# MedHubV1.net
KiCad netlist of a schematic drawn in EAGLE
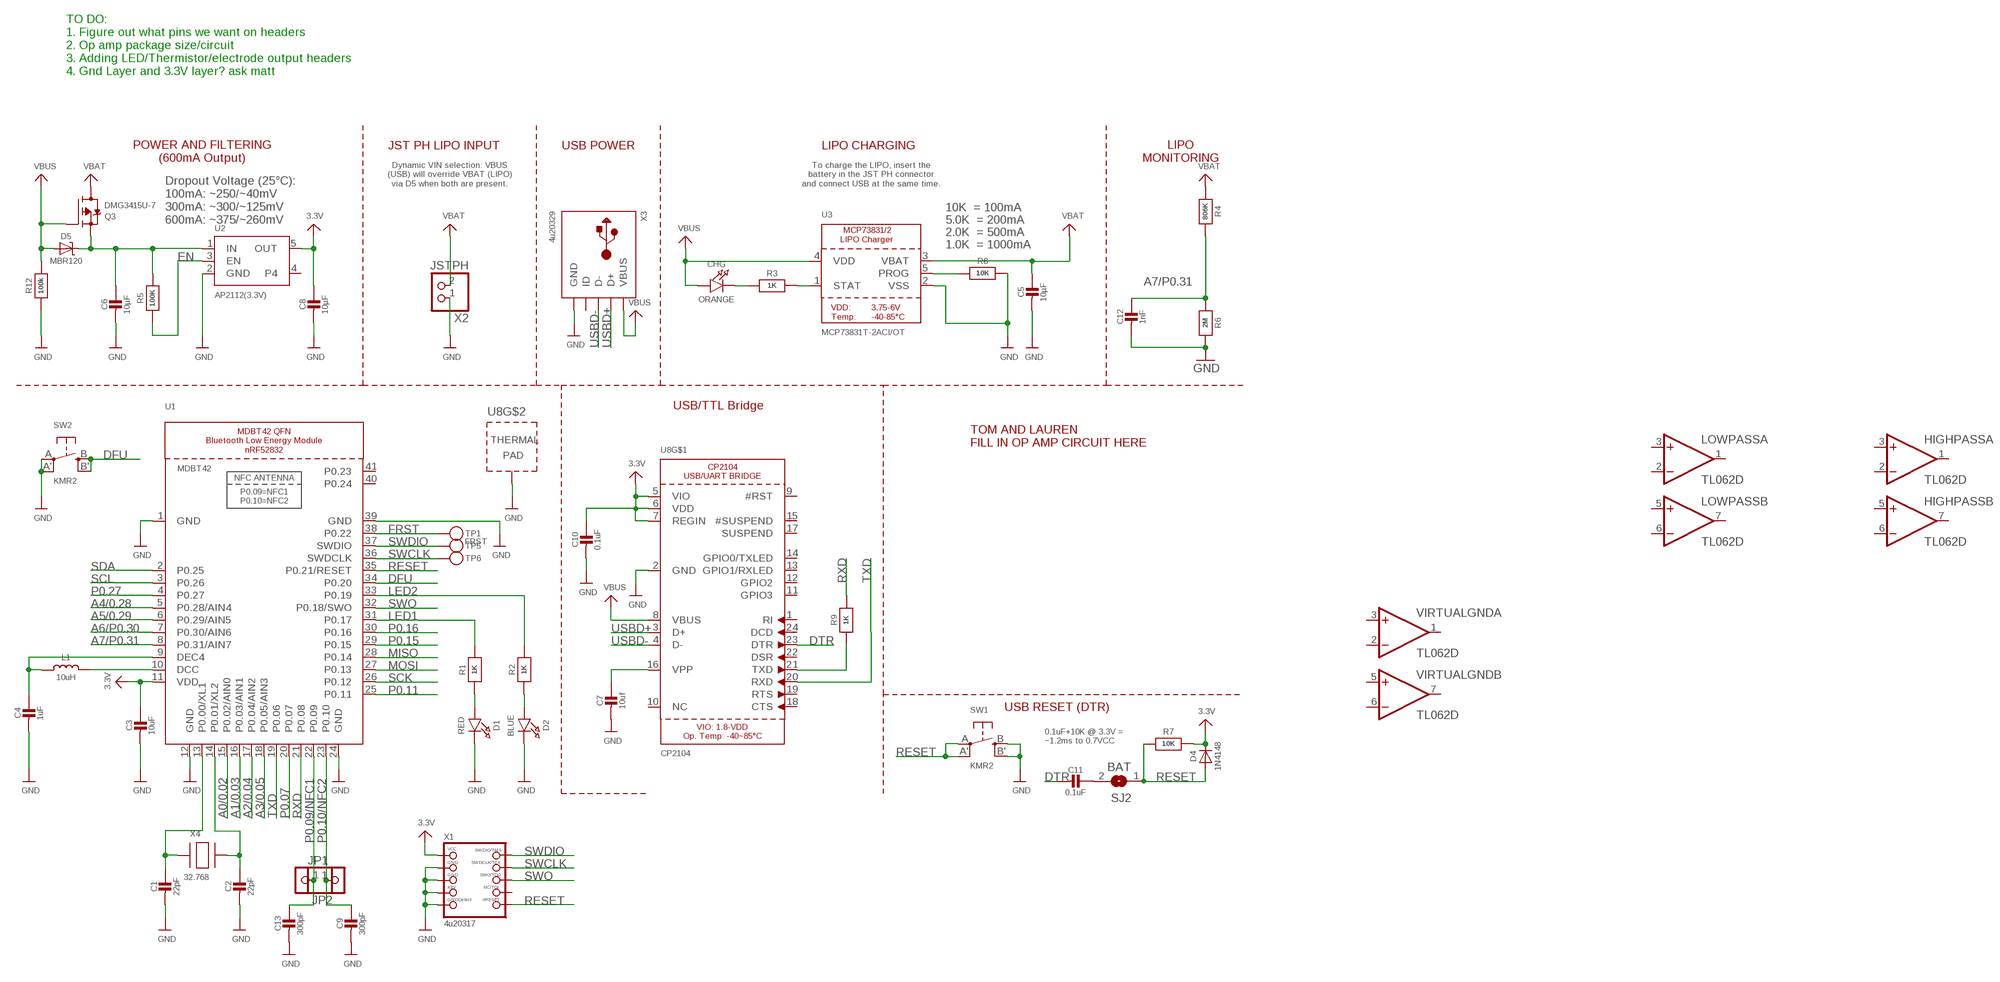
[diagram p0: schematic, sheet 1]

(export (version "E")
  (design (tool "Eeschema 10.0.6"))
  (components
    (comp (ref "C1")
      (value "22pF")
      (footprint "eagle-import:0603-NO")
      (libsource (lib "eagle-import") (part "CAP_CERAMIC0603_NO"))
    )
    (comp (ref "C2")
      (value "22pF")
      (footprint "eagle-import:0603-NO")
      (libsource (lib "eagle-import") (part "CAP_CERAMIC0603_NO"))
    )
    (comp (ref "C3")
      (value "10uF")
      (footprint "eagle-import:0805-NO")
      (libsource (lib "eagle-import") (part "CAP_CERAMIC0805-NOOUTLINE"))
    )
    (comp (ref "C4")
      (value "1uF")
      (footprint "eagle-import:0603-NO")
      (libsource (lib "eagle-import") (part "CAP_CERAMIC0603_NO"))
    )
    (comp (ref "C5")
      (value "10µF")
      (footprint "eagle-import:0805-NO")
      (libsource (lib "eagle-import") (part "CAP_CERAMIC0805-NOOUTLINE"))
    )
    (comp (ref "C6")
      (value "10µF")
      (footprint "eagle-import:0805-NO")
      (libsource (lib "eagle-import") (part "CAP_CERAMIC0805-NOOUTLINE"))
    )
    (comp (ref "C7")
      (value "10uf")
      (footprint "eagle-import:0805-NO")
      (libsource (lib "eagle-import") (part "CAP_CERAMIC0805-NOOUTLINE"))
    )
    (comp (ref "C8")
      (value "10µF")
      (footprint "eagle-import:0805-NO")
      (libsource (lib "eagle-import") (part "CAP_CERAMIC0805-NOOUTLINE"))
    )
    (comp (ref "C9")
      (value "300pF")
      (footprint "eagle-import:_0603MP")
      (libsource (lib "eagle-import") (part "CAP_CERAMIC_0603MP"))
    )
    (comp (ref "C10")
      (value "0.1uF")
      (footprint "eagle-import:0603-NO")
      (libsource (lib "eagle-import") (part "CAP_CERAMIC0603_NO"))
    )
    (comp (ref "C11")
      (value "0.1uF")
      (footprint "eagle-import:0603-NO")
      (libsource (lib "eagle-import") (part "CAP_CERAMIC0603_NO"))
    )
    (comp (ref "C12")
      (value "1nF")
      (footprint "eagle-import:0603-NO")
      (libsource (lib "eagle-import") (part "CAP_CERAMIC0603_NO"))
    )
    (comp (ref "C13")
      (value "300pF")
      (footprint "eagle-import:_0603MP")
      (libsource (lib "eagle-import") (part "CAP_CERAMIC_0603MP"))
    )
    (comp (ref "CHG")
      (value "ORANGE")
      (footprint "eagle-import:CHIPLED_0805_NOOUTLINE")
      (libsource (lib "eagle-import") (part "LED0805_NOOUTLINE"))
    )
    (comp (ref "D1")
      (value "RED")
      (footprint "eagle-import:CHIPLED_0805_NOOUTLINE")
      (libsource (lib "eagle-import") (part "LED0805_NOOUTLINE"))
    )
    (comp (ref "D2")
      (value "BLUE")
      (footprint "eagle-import:CHIPLED_0805_NOOUTLINE")
      (libsource (lib "eagle-import") (part "LED0805_NOOUTLINE"))
    )
    (comp (ref "D4")
      (value "1N4148")
      (footprint "eagle-import:SOD-323")
      (libsource (lib "eagle-import") (part "DIODESOD-323"))
    )
    (comp (ref "D5")
      (value "MBR120")
      (footprint "eagle-import:SOD-123")
      (libsource (lib "eagle-import") (part "DIODE-SCHOTTKYSOD-123"))
    )
    (comp (ref "HIGHPASS")
      (value "TL062D")
      (footprint "eagle-import:SO08")
      (libsource (lib "eagle-import") (part "TL062D"))
    )
    (comp (ref "JP1")
      (value "HEADER-1X12MM")
      (footprint "eagle-import:1X01_2MM")
      (libsource (lib "eagle-import") (part "HEADER-1X12MM"))
    )
    (comp (ref "JP2")
      (value "HEADER-1X12MM")
      (footprint "eagle-import:1X01_2MM")
      (libsource (lib "eagle-import") (part "HEADER-1X12MM"))
    )
    (comp (ref "L1")
      (value "10uH")
      (footprint "eagle-import:0805-NO")
      (libsource (lib "eagle-import") (part "INDUCTOR0805-NO"))
    )
    (comp (ref "LOWPASS")
      (value "TL062D")
      (footprint "eagle-import:SO08")
      (libsource (lib "eagle-import") (part "TL062D"))
    )
    (comp (ref "Q3")
      (value "DMG3415U-7")
      (footprint "eagle-import:SOT23-R")
      (libsource (lib "eagle-import") (part "MOSFET-P"))
    )
    (comp (ref "R1")
      (value "1K")
      (footprint "eagle-import:0603-NO")
      (libsource (lib "eagle-import") (part "RESISTOR_0603_NOOUT"))
    )
    (comp (ref "R2")
      (value "1K")
      (footprint "eagle-import:0603-NO")
      (libsource (lib "eagle-import") (part "RESISTOR_0603_NOOUT"))
    )
    (comp (ref "R3")
      (value "1K")
      (footprint "eagle-import:0603-NO")
      (libsource (lib "eagle-import") (part "RESISTOR_0603_NOOUT"))
    )
    (comp (ref "R4")
      (value "806K")
      (footprint "eagle-import:0603-NO")
      (libsource (lib "eagle-import") (part "RESISTOR_0603_NOOUT"))
    )
    (comp (ref "R5")
      (value "100K")
      (footprint "eagle-import:0603-NO")
      (libsource (lib "eagle-import") (part "RESISTOR_0603_NOOUT"))
    )
    (comp (ref "R6")
      (value "2M")
      (footprint "eagle-import:0603-NO")
      (libsource (lib "eagle-import") (part "RESISTOR_0603_NOOUT"))
    )
    (comp (ref "R7")
      (value "10K")
      (footprint "eagle-import:0603-NO")
      (libsource (lib "eagle-import") (part "RESISTOR_0603_NOOUT"))
    )
    (comp (ref "R8")
      (value "10K")
      (footprint "eagle-import:0603-NO")
      (libsource (lib "eagle-import") (part "RESISTOR_0603_NOOUT"))
    )
    (comp (ref "R9")
      (value "1K")
      (footprint "eagle-import:0603-NO")
      (libsource (lib "eagle-import") (part "RESISTOR_0603_NOOUT"))
    )
    (comp (ref "R12")
      (value "100k")
      (footprint "eagle-import:0603-NO")
      (libsource (lib "eagle-import") (part "RESISTOR_0603_NOOUT"))
    )
    (comp (ref "SJ2")
      (value "BAT")
      (footprint "eagle-import:SOLDERJUMPER_CLOSEDWIRE")
      (libsource (lib "eagle-import") (part "SOLDERJUMPERCLOSED"))
    )
    (comp (ref "SW1")
      (value "KMR2")
      (footprint "eagle-import:BTN_KMR2_4.6X2.8")
      (libsource (lib "eagle-import") (part "SWITCH_TACT_SMT4.6X2.8"))
    )
    (comp (ref "SW2")
      (value "KMR2")
      (footprint "eagle-import:BTN_KMR2_4.6X2.8")
      (libsource (lib "eagle-import") (part "SWITCH_TACT_SMT4.6X2.8"))
    )
    (comp (ref "TP1")
      (value "FRST")
      (footprint "eagle-import:PAD-1.5X2.0")
      (libsource (lib "eagle-import") (part "TESTPOINT1.5X2.0MM_NOCREAM"))
    )
    (comp (ref "TP5")
      (value "TESTPOINTROUND2MM")
      (footprint "eagle-import:TESTPOINT_ROUND_2MM")
      (libsource (lib "eagle-import") (part "TESTPOINTROUND2MM"))
    )
    (comp (ref "TP6")
      (value "TESTPOINTROUND2MM")
      (footprint "eagle-import:TESTPOINT_ROUND_2MM")
      (libsource (lib "eagle-import") (part "TESTPOINTROUND2MM"))
    )
    (comp (ref "U1")
      (value "MDBT42")
      (footprint "eagle-import:BLE_MODULE_RAYTAC_MDBT42")
      (libsource (lib "eagle-import") (part "NRF52832_MODULE_MDBT42"))
    )
    (comp (ref "U2")
      (value "AP2112(3.3V)")
      (footprint "eagle-import:SOT23-5")
      (libsource (lib "eagle-import") (part "VREG_SOT23-5"))
    )
    (comp (ref "U3")
      (value "MCP73831T-2ACI/OT")
      (footprint "eagle-import:SOT23-5")
      (libsource (lib "eagle-import") (part "MCP73831/2"))
    )
    (comp (ref "U8")
      (value "CP2104")
      (footprint "eagle-import:QFN24_4MM_SMSC")
      (libsource (lib "eagle-import") (part "CP2104"))
    )
    (comp (ref "VIRTUALGND")
      (value "TL062D")
      (footprint "eagle-import:SO08")
      (libsource (lib "eagle-import") (part "TL062D"))
    )
    (comp (ref "X1")
      (value "4u20317")
      (footprint "eagle-import:2X05_1.27MM_BOX_POSTS")
      (libsource (lib "eagle-import") (part "JTAG-CORTEXBOXPOSTS"))
    )
    (comp (ref "X2")
      (value "JSTPH")
      (footprint "eagle-import:JSTPH2")
      (libsource (lib "eagle-import") (part "CON_JST_PH_2PIN"))
    )
    (comp (ref "X3")
      (value "4u20329")
      (footprint "eagle-import:4UCONN_20329_V2")
      (libsource (lib "eagle-import") (part "USB_MICRO_20329_V2"))
    )
    (comp (ref "X4")
      (value "32.768")
      (footprint "eagle-import:XTAL3215")
      (libsource (lib "eagle-import") (part "XTAL-3.2X1.5"))
    )
  )
  (nets
    (net (code "1") (name "/A0{slash}0.02") (class "Default")
      (node (ref "U1") (pin "15") (pinfunction "P0.02/AIN0_15") (pintype "bidirectional"))
    )
    (net (code "2") (name "/A1{slash}0.03") (class "Default")
      (node (ref "U1") (pin "16") (pinfunction "P0.03/AIN1_16") (pintype "bidirectional"))
    )
    (net (code "3") (name "/A2{slash}0.04") (class "Default")
      (node (ref "U1") (pin "17") (pinfunction "P0.04/AIN2_17") (pintype "bidirectional"))
    )
    (net (code "4") (name "/A3{slash}0.05") (class "Default")
      (node (ref "U1") (pin "18") (pinfunction "P0.05/AIN3_18") (pintype "bidirectional"))
    )
    (net (code "5") (name "/A4{slash}0.28") (class "Default")
      (node (ref "U1") (pin "5") (pinfunction "P0.28/AIN4_5") (pintype "bidirectional"))
    )
    (net (code "6") (name "/A5{slash}0.29") (class "Default")
      (node (ref "U1") (pin "6") (pinfunction "P0.29/AIN5_6") (pintype "bidirectional"))
    )
    (net (code "7") (name "/A6{slash}P0.30") (class "Default")
      (node (ref "U1") (pin "7") (pinfunction "P0.30/AIN6_7") (pintype "bidirectional"))
    )
    (net (code "8") (name "/A7{slash}P0.31") (class "Default")
      (node (ref "C12") (pin "1") (pinfunction "1_1") (pintype "passive"))
      (node (ref "R4") (pin "2") (pinfunction "2_2") (pintype "passive"))
      (node (ref "R6") (pin "1") (pinfunction "1_1") (pintype "passive"))
      (node (ref "U1") (pin "8") (pinfunction "P0.31/AIN7_8") (pintype "bidirectional"))
    )
    (net (code "9") (name "/DFU") (class "Default")
      (node (ref "SW2") (pin "B") (pinfunction "S_B") (pintype "passive"))
      (node (ref "SW2") (pin "B'") (pinfunction "S1_B'") (pintype "passive"))
      (node (ref "U1") (pin "34") (pinfunction "P0.20_34") (pintype "bidirectional"))
    )
    (net (code "10") (name "/DTR") (class "Default")
      (node (ref "C11") (pin "2") (pinfunction "2_2") (pintype "passive"))
      (node (ref "U8") (pin "23") (pinfunction "DTR_23") (pintype "output"))
    )
    (net (code "11") (name "/EN") (class "Default")
      (node (ref "R5") (pin "1") (pinfunction "1_1") (pintype "passive"))
      (node (ref "U2") (pin "3") (pinfunction "EN_3") (pintype "input"))
    )
    (net (code "12") (name "/FRST") (class "Default")
      (node (ref "TP1") (pin "P$1") (pinfunction "P$1_P$1") (pintype "bidirectional"))
      (node (ref "U1") (pin "38") (pinfunction "P0.22_38") (pintype "bidirectional"))
    )
    (net (code "13") (name "/LED1") (class "Default")
      (node (ref "R1") (pin "2") (pinfunction "2_2") (pintype "passive"))
      (node (ref "U1") (pin "31") (pinfunction "P0.17_31") (pintype "bidirectional"))
    )
    (net (code "14") (name "/LED2") (class "Default")
      (node (ref "R2") (pin "2") (pinfunction "2_2") (pintype "passive"))
      (node (ref "U1") (pin "33") (pinfunction "P0.19_33") (pintype "bidirectional"))
    )
    (net (code "15") (name "/MISO") (class "Default")
      (node (ref "U1") (pin "28") (pinfunction "P0.14_28") (pintype "bidirectional"))
    )
    (net (code "16") (name "/MOSI") (class "Default")
      (node (ref "U1") (pin "27") (pinfunction "P0.13_27") (pintype "bidirectional"))
    )
    (net (code "17") (name "/P0.07") (class "Default")
      (node (ref "U1") (pin "20") (pinfunction "P0.07_20") (pintype "bidirectional"))
    )
    (net (code "18") (name "/P0.09{slash}NFC1") (class "Default")
      (node (ref "C13") (pin "1") (pinfunction "1_1") (pintype "passive"))
      (node (ref "JP2") (pin "1") (pinfunction "1_1") (pintype "passive"))
      (node (ref "U1") (pin "22") (pinfunction "P0.09_22") (pintype "bidirectional"))
    )
    (net (code "19") (name "/P0.10{slash}NFC2") (class "Default")
      (node (ref "C9") (pin "1") (pinfunction "1_1") (pintype "passive"))
      (node (ref "JP1") (pin "1") (pinfunction "1_1") (pintype "passive"))
      (node (ref "U1") (pin "23") (pinfunction "P0.10_23") (pintype "bidirectional"))
    )
    (net (code "20") (name "/P0.11") (class "Default")
      (node (ref "U1") (pin "25") (pinfunction "P0.11_25") (pintype "bidirectional"))
    )
    (net (code "21") (name "/P0.15") (class "Default")
      (node (ref "U1") (pin "29") (pinfunction "P0.15_29") (pintype "bidirectional"))
    )
    (net (code "22") (name "/P0.16") (class "Default")
      (node (ref "U1") (pin "30") (pinfunction "P0.16_30") (pintype "bidirectional"))
    )
    (net (code "23") (name "/P0.27") (class "Default")
      (node (ref "U1") (pin "4") (pinfunction "P0.27_4") (pintype "bidirectional"))
    )
    (net (code "24") (name "/RESET") (class "Default")
      (node (ref "D4") (pin "A") (pinfunction "A_A") (pintype "passive"))
      (node (ref "R7") (pin "1") (pinfunction "1_1") (pintype "passive"))
      (node (ref "SJ2") (pin "1") (pinfunction "1_1") (pintype "passive"))
      (node (ref "SW1") (pin "A") (pinfunction "P_A") (pintype "passive"))
      (node (ref "SW1") (pin "A'") (pinfunction "P1_A'") (pintype "passive"))
      (node (ref "U1") (pin "35") (pinfunction "P0.21/RESET_35") (pintype "bidirectional"))
      (node (ref "X1") (pin "10") (pinfunction "NRESET_10") (pintype "bidirectional"))
    )
    (net (code "25") (name "/RXD") (class "Default")
      (node (ref "R9") (pin "2") (pinfunction "2_2") (pintype "passive"))
      (node (ref "U1") (pin "21") (pinfunction "P0.08_21") (pintype "bidirectional"))
    )
    (net (code "26") (name "/SCK") (class "Default")
      (node (ref "U1") (pin "26") (pinfunction "P0.12_26") (pintype "bidirectional"))
    )
    (net (code "27") (name "/SCL") (class "Default")
      (node (ref "U1") (pin "3") (pinfunction "P0.26_3") (pintype "bidirectional"))
    )
    (net (code "28") (name "/SDA") (class "Default")
      (node (ref "U1") (pin "2") (pinfunction "P0.25_2") (pintype "bidirectional"))
    )
    (net (code "29") (name "/SWCLK") (class "Default")
      (node (ref "TP6") (pin "P$1") (pinfunction "P$1_P$1") (pintype "bidirectional"))
      (node (ref "U1") (pin "36") (pinfunction "SWDCLK_36") (pintype "bidirectional"))
      (node (ref "X1") (pin "4") (pinfunction "SWDCLK_4") (pintype "bidirectional"))
    )
    (net (code "30") (name "/SWDIO") (class "Default")
      (node (ref "TP5") (pin "P$1") (pinfunction "P$1_P$1") (pintype "bidirectional"))
      (node (ref "U1") (pin "37") (pinfunction "SWDIO_37") (pintype "bidirectional"))
      (node (ref "X1") (pin "2") (pinfunction "SWDIO_2") (pintype "bidirectional"))
    )
    (net (code "31") (name "/SWO") (class "Default")
      (node (ref "U1") (pin "32") (pinfunction "P0.18/SWO_32") (pintype "bidirectional"))
      (node (ref "X1") (pin "6") (pinfunction "SWO_6") (pintype "bidirectional"))
    )
    (net (code "32") (name "/TXD") (class "Default")
      (node (ref "U1") (pin "19") (pinfunction "P0.06_19") (pintype "bidirectional"))
      (node (ref "U8") (pin "20") (pinfunction "RXD_20") (pintype "input"))
    )
    (net (code "33") (name "/USBD+") (class "Default")
      (node (ref "U8") (pin "3") (pinfunction "D+_3") (pintype "bidirectional"))
      (node (ref "X3") (pin "D+") (pinfunction "D+_D+") (pintype "bidirectional"))
    )
    (net (code "34") (name "/USBD-") (class "Default")
      (node (ref "U8") (pin "4") (pinfunction "D-_4") (pintype "bidirectional"))
      (node (ref "X3") (pin "D-") (pinfunction "D-_D-") (pintype "bidirectional"))
    )
    (net (code "35") (name "3.3V") (class "Default")
      (node (ref "C10") (pin "1") (pinfunction "1_1") (pintype "passive"))
      (node (ref "C3") (pin "1") (pinfunction "1_1") (pintype "passive"))
      (node (ref "C8") (pin "1") (pinfunction "1_1") (pintype "passive"))
      (node (ref "D4") (pin "C") (pinfunction "C_C") (pintype "passive"))
      (node (ref "R7") (pin "2") (pinfunction "2_2") (pintype "passive"))
      (node (ref "U1") (pin "11") (pinfunction "VDD_11") (pintype "bidirectional"))
      (node (ref "U2") (pin "5") (pinfunction "OUT_5") (pintype "power_in"))
      (node (ref "U8") (pin "5") (pinfunction "VIO_5") (pintype "power_in"))
      (node (ref "U8") (pin "6") (pinfunction "VDD_6") (pintype "power_in"))
      (node (ref "U8") (pin "7") (pinfunction "REGIN_7") (pintype "power_in"))
      (node (ref "X1") (pin "1") (pinfunction "VCC_1") (pintype "power_in"))
    )
    (net (code "36") (name "GND") (class "Default")
      (node (ref "C1") (pin "2") (pinfunction "2_2") (pintype "passive"))
      (node (ref "C10") (pin "2") (pinfunction "2_2") (pintype "passive"))
      (node (ref "C12") (pin "2") (pinfunction "2_2") (pintype "passive"))
      (node (ref "C13") (pin "2") (pinfunction "2_2") (pintype "passive"))
      (node (ref "C2") (pin "2") (pinfunction "2_2") (pintype "passive"))
      (node (ref "C3") (pin "2") (pinfunction "2_2") (pintype "passive"))
      (node (ref "C4") (pin "2") (pinfunction "2_2") (pintype "passive"))
      (node (ref "C5") (pin "2") (pinfunction "2_2") (pintype "passive"))
      (node (ref "C6") (pin "2") (pinfunction "2_2") (pintype "passive"))
      (node (ref "C7") (pin "2") (pinfunction "2_2") (pintype "passive"))
      (node (ref "C8") (pin "2") (pinfunction "2_2") (pintype "passive"))
      (node (ref "C9") (pin "2") (pinfunction "2_2") (pintype "passive"))
      (node (ref "D1") (pin "C") (pinfunction "C_C") (pintype "passive"))
      (node (ref "D2") (pin "C") (pinfunction "C_C") (pintype "passive"))
      (node (ref "R12") (pin "1") (pinfunction "1_1") (pintype "passive"))
      (node (ref "R6") (pin "2") (pinfunction "2_2") (pintype "passive"))
      (node (ref "R8") (pin "2") (pinfunction "2_2") (pintype "passive"))
      (node (ref "SW1") (pin "B") (pinfunction "S_B") (pintype "passive"))
      (node (ref "SW1") (pin "B'") (pinfunction "S1_B'") (pintype "passive"))
      (node (ref "SW2") (pin "A") (pinfunction "P_A") (pintype "passive"))
      (node (ref "SW2") (pin "A'") (pinfunction "P1_A'") (pintype "passive"))
      (node (ref "U1") (pin "1") (pinfunction "GND_1") (pintype "bidirectional"))
      (node (ref "U1") (pin "12") (pinfunction "GND_12") (pintype "bidirectional"))
      (node (ref "U1") (pin "24") (pinfunction "GND_24") (pintype "bidirectional"))
      (node (ref "U1") (pin "39") (pinfunction "GND_39") (pintype "bidirectional"))
      (node (ref "U2") (pin "2") (pinfunction "GND_2") (pintype "power_in"))
      (node (ref "U3") (pin "2") (pinfunction "VSS_2") (pintype "power_in"))
      (node (ref "U8") (pin "2") (pinfunction "GND_2") (pintype "power_in"))
      (node (ref "U8") (pin "THERM") (pinfunction "TP_THERM") (pintype "power_in"))
      (node (ref "X1") (pin "3") (pinfunction "GND_3") (pintype "power_in"))
      (node (ref "X1") (pin "5") (pinfunction "GND_5") (pintype "power_in"))
      (node (ref "X1") (pin "7") (pinfunction "KEY_7") (pintype "bidirectional"))
      (node (ref "X1") (pin "9") (pinfunction "GNDDETECT_9") (pintype "bidirectional"))
      (node (ref "X2") (pin "1") (pinfunction "1_1") (pintype "passive"))
      (node (ref "X3") (pin "BASE@1") (pinfunction "GND_BASE@1") (pintype "power_in"))
      (node (ref "X3") (pin "BASE@2") (pinfunction "GND_BASE@2") (pintype "power_in"))
      (node (ref "X3") (pin "GND") (pinfunction "GND_GND") (pintype "power_in"))
      (node (ref "X3") (pin "SPRT@1") (pinfunction "GND_SPRT@1") (pintype "power_in"))
      (node (ref "X3") (pin "SPRT@2") (pinfunction "GND_SPRT@2") (pintype "power_in"))
      (node (ref "X3") (pin "SPRT@3") (pinfunction "GND_SPRT@3") (pintype "power_in"))
      (node (ref "X3") (pin "SPRT@4") (pinfunction "GND_SPRT@4") (pintype "power_in"))
    )
    (net (code "37") (name "Net-(C11-Pad1)") (class "Default")
      (node (ref "C11") (pin "1") (pinfunction "1_1") (pintype "passive"))
      (node (ref "SJ2") (pin "2") (pinfunction "2_2") (pintype "passive"))
    )
    (net (code "38") (name "Net-(CHG-PadC)") (class "Default")
      (node (ref "CHG") (pin "C") (pinfunction "C_C") (pintype "passive"))
      (node (ref "R3") (pin "1") (pinfunction "1_1") (pintype "passive"))
    )
    (net (code "39") (name "Net-(D1-PadA)") (class "Default")
      (node (ref "D1") (pin "A") (pinfunction "A_A") (pintype "passive"))
      (node (ref "R1") (pin "1") (pinfunction "1_1") (pintype "passive"))
    )
    (net (code "40") (name "Net-(D2-PadA)") (class "Default")
      (node (ref "D2") (pin "A") (pinfunction "A_A") (pintype "passive"))
      (node (ref "R2") (pin "1") (pinfunction "1_1") (pintype "passive"))
    )
    (net (code "41") (name "Net-(Q3-S)") (class "Default")
      (node (ref "C6") (pin "1") (pinfunction "1_1") (pintype "passive"))
      (node (ref "D5") (pin "C") (pinfunction "C_C") (pintype "passive"))
      (node (ref "Q3") (pin "2") (pinfunction "S_2") (pintype "passive"))
      (node (ref "R5") (pin "2") (pinfunction "2_2") (pintype "passive"))
      (node (ref "U2") (pin "1") (pinfunction "IN_1") (pintype "power_in"))
    )
    (net (code "42") (name "Net-(U1-DCC)") (class "Default")
      (node (ref "L1") (pin "2") (pinfunction "2_2") (pintype "passive"))
      (node (ref "U1") (pin "10") (pinfunction "DCC_10") (pintype "bidirectional"))
    )
    (net (code "43") (name "Net-(U1-DEC4)") (class "Default")
      (node (ref "C4") (pin "1") (pinfunction "1_1") (pintype "passive"))
      (node (ref "L1") (pin "1") (pinfunction "1_1") (pintype "passive"))
      (node (ref "U1") (pin "9") (pinfunction "DEC4_9") (pintype "bidirectional"))
    )
    (net (code "44") (name "Net-(U1-P0.00{slash}XL1)") (class "Default")
      (node (ref "C1") (pin "1") (pinfunction "1_1") (pintype "passive"))
      (node (ref "U1") (pin "13") (pinfunction "P0.00/XL1_13") (pintype "bidirectional"))
      (node (ref "X4") (pin "P$1") (pinfunction "P$1_P$1") (pintype "bidirectional"))
    )
    (net (code "45") (name "Net-(U1-P0.01{slash}XL2)") (class "Default")
      (node (ref "C2") (pin "1") (pinfunction "1_1") (pintype "passive"))
      (node (ref "U1") (pin "14") (pinfunction "P0.01/XL2_14") (pintype "bidirectional"))
      (node (ref "X4") (pin "P$2") (pinfunction "P$2_P$2") (pintype "bidirectional"))
    )
    (net (code "46") (name "Net-(U3-PROG)") (class "Default")
      (node (ref "R8") (pin "1") (pinfunction "1_1") (pintype "passive"))
      (node (ref "U3") (pin "5") (pinfunction "PROG_5") (pintype "input"))
    )
    (net (code "47") (name "Net-(U3-STAT)") (class "Default")
      (node (ref "R3") (pin "2") (pinfunction "2_2") (pintype "passive"))
      (node (ref "U3") (pin "1") (pinfunction "STAT_1") (pintype "output"))
    )
    (net (code "48") (name "Net-(U8A-TXD)") (class "Default")
      (node (ref "R9") (pin "1") (pinfunction "1_1") (pintype "passive"))
      (node (ref "U8") (pin "21") (pinfunction "TXD_21") (pintype "output"))
    )
    (net (code "49") (name "Net-(U8A-VPP)") (class "Default")
      (node (ref "C7") (pin "1") (pinfunction "1_1") (pintype "passive"))
      (node (ref "U8") (pin "16") (pinfunction "VPP_16") (pintype "bidirectional"))
    )
    (net (code "50") (name "VBAT") (class "Default")
      (node (ref "C5") (pin "1") (pinfunction "1_1") (pintype "passive"))
      (node (ref "Q3") (pin "3") (pinfunction "D_3") (pintype "passive"))
      (node (ref "R4") (pin "1") (pinfunction "1_1") (pintype "passive"))
      (node (ref "U3") (pin "3") (pinfunction "VBAT_3") (pintype "power_in"))
      (node (ref "X2") (pin "2") (pinfunction "2_2") (pintype "passive"))
    )
    (net (code "51") (name "VBUS") (class "Default")
      (node (ref "CHG") (pin "A") (pinfunction "A_A") (pintype "passive"))
      (node (ref "D5") (pin "A") (pinfunction "A_A") (pintype "passive"))
      (node (ref "Q3") (pin "1") (pinfunction "G_1") (pintype "passive"))
      (node (ref "R12") (pin "2") (pinfunction "2_2") (pintype "passive"))
      (node (ref "U3") (pin "4") (pinfunction "VDD_4") (pintype "power_in"))
      (node (ref "U8") (pin "8") (pinfunction "VBUS_8") (pintype "power_in"))
      (node (ref "X3") (pin "VBUS") (pinfunction "VBUS_VBUS") (pintype "power_in"))
    )
    (net (code "52") (name "unconnected-(HIGHPASSA-+IN-Pad3)") (class "Default")
      (node (ref "HIGHPASS") (pin "3") (pinfunction "+IN_3") (pintype "input"))
    )
    (net (code "53") (name "unconnected-(HIGHPASSA--IN-Pad2)") (class "Default")
      (node (ref "HIGHPASS") (pin "2") (pinfunction "-IN_2") (pintype "input"))
    )
    (net (code "54") (name "unconnected-(HIGHPASSA-OUT-Pad1)") (class "Default")
      (node (ref "HIGHPASS") (pin "1") (pinfunction "OUT_1") (pintype "output"))
    )
    (net (code "55") (name "unconnected-(HIGHPASSB-+IN-Pad5)") (class "Default")
      (node (ref "HIGHPASS") (pin "5") (pinfunction "+IN_5") (pintype "input"))
    )
    (net (code "56") (name "unconnected-(HIGHPASSB--IN-Pad6)") (class "Default")
      (node (ref "HIGHPASS") (pin "6") (pinfunction "-IN_6") (pintype "input"))
    )
    (net (code "57") (name "unconnected-(HIGHPASSB-OUT-Pad7)") (class "Default")
      (node (ref "HIGHPASS") (pin "7") (pinfunction "OUT_7") (pintype "output"))
    )
    (net (code "58") (name "unconnected-(LOWPASSA-+IN-Pad3)") (class "Default")
      (node (ref "LOWPASS") (pin "3") (pinfunction "+IN_3") (pintype "input"))
    )
    (net (code "59") (name "unconnected-(LOWPASSA--IN-Pad2)") (class "Default")
      (node (ref "LOWPASS") (pin "2") (pinfunction "-IN_2") (pintype "input"))
    )
    (net (code "60") (name "unconnected-(LOWPASSA-OUT-Pad1)") (class "Default")
      (node (ref "LOWPASS") (pin "1") (pinfunction "OUT_1") (pintype "output"))
    )
    (net (code "61") (name "unconnected-(LOWPASSB-+IN-Pad5)") (class "Default")
      (node (ref "LOWPASS") (pin "5") (pinfunction "+IN_5") (pintype "input"))
    )
    (net (code "62") (name "unconnected-(LOWPASSB--IN-Pad6)") (class "Default")
      (node (ref "LOWPASS") (pin "6") (pinfunction "-IN_6") (pintype "input"))
    )
    (net (code "63") (name "unconnected-(LOWPASSB-OUT-Pad7)") (class "Default")
      (node (ref "LOWPASS") (pin "7") (pinfunction "OUT_7") (pintype "output"))
    )
    (net (code "64") (name "unconnected-(U1-P0.23-Pad41)") (class "Default")
      (node (ref "U1") (pin "41") (pinfunction "P0.23_41") (pintype "bidirectional"))
    )
    (net (code "65") (name "unconnected-(U1-P0.24-Pad40)") (class "Default")
      (node (ref "U1") (pin "40") (pinfunction "P0.24_40") (pintype "bidirectional"))
    )
    (net (code "66") (name "unconnected-(U2-P4-Pad4)") (class "Default")
      (node (ref "U2") (pin "4") (pinfunction "P4_4") (pintype "bidirectional"))
    )
    (net (code "67") (name "unconnected-(U8A-#RST-Pad9)") (class "Default")
      (node (ref "U8") (pin "9") (pinfunction "#RST_9") (pintype "bidirectional"))
    )
    (net (code "68") (name "unconnected-(U8A-#SUSPEND-Pad15)") (class "Default")
      (node (ref "U8") (pin "15") (pinfunction "#SUSPEND_15") (pintype "output"))
    )
    (net (code "69") (name "unconnected-(U8A-CTS-Pad18)") (class "Default")
      (node (ref "U8") (pin "18") (pinfunction "CTS_18") (pintype "input"))
    )
    (net (code "70") (name "unconnected-(U8A-DCD-Pad24)") (class "Default")
      (node (ref "U8") (pin "24") (pinfunction "DCD_24") (pintype "input"))
    )
    (net (code "71") (name "unconnected-(U8A-DSR-Pad22)") (class "Default")
      (node (ref "U8") (pin "22") (pinfunction "DSR_22") (pintype "input"))
    )
    (net (code "72") (name "unconnected-(U8A-GPIO0{slash}TXLED-Pad14)") (class "Default")
      (node (ref "U8") (pin "14") (pinfunction "GPIO0/TXLED_14") (pintype "bidirectional"))
    )
    (net (code "73") (name "unconnected-(U8A-GPIO1{slash}RXLED-Pad13)") (class "Default")
      (node (ref "U8") (pin "13") (pinfunction "GPIO1/RXLED_13") (pintype "bidirectional"))
    )
    (net (code "74") (name "unconnected-(U8A-GPIO2-Pad12)") (class "Default")
      (node (ref "U8") (pin "12") (pinfunction "GPIO2_12") (pintype "bidirectional"))
    )
    (net (code "75") (name "unconnected-(U8A-GPIO3-Pad11)") (class "Default")
      (node (ref "U8") (pin "11") (pinfunction "GPIO3_11") (pintype "bidirectional"))
    )
    (net (code "76") (name "unconnected-(U8A-NC-Pad10)") (class "Default")
      (node (ref "U8") (pin "10") (pinfunction "NC_10") (pintype "no_connect"))
    )
    (net (code "77") (name "unconnected-(U8A-RI-Pad1)") (class "Default")
      (node (ref "U8") (pin "1") (pinfunction "RI_1") (pintype "input"))
    )
    (net (code "78") (name "unconnected-(U8A-RTS-Pad19)") (class "Default")
      (node (ref "U8") (pin "19") (pinfunction "RTS_19") (pintype "output"))
    )
    (net (code "79") (name "unconnected-(U8A-SUSPEND-Pad17)") (class "Default")
      (node (ref "U8") (pin "17") (pinfunction "SUSPEND_17") (pintype "output"))
    )
    (net (code "80") (name "unconnected-(VIRTUALGNDA-+IN-Pad3)") (class "Default")
      (node (ref "VIRTUALGND") (pin "3") (pinfunction "+IN_3") (pintype "input"))
    )
    (net (code "81") (name "unconnected-(VIRTUALGNDA--IN-Pad2)") (class "Default")
      (node (ref "VIRTUALGND") (pin "2") (pinfunction "-IN_2") (pintype "input"))
    )
    (net (code "82") (name "unconnected-(VIRTUALGNDA-OUT-Pad1)") (class "Default")
      (node (ref "VIRTUALGND") (pin "1") (pinfunction "OUT_1") (pintype "output"))
    )
    (net (code "83") (name "unconnected-(VIRTUALGNDB-+IN-Pad5)") (class "Default")
      (node (ref "VIRTUALGND") (pin "5") (pinfunction "+IN_5") (pintype "input"))
    )
    (net (code "84") (name "unconnected-(VIRTUALGNDB--IN-Pad6)") (class "Default")
      (node (ref "VIRTUALGND") (pin "6") (pinfunction "-IN_6") (pintype "input"))
    )
    (net (code "85") (name "unconnected-(VIRTUALGNDB-OUT-Pad7)") (class "Default")
      (node (ref "VIRTUALGND") (pin "7") (pinfunction "OUT_7") (pintype "output"))
    )
    (net (code "86") (name "unconnected-(X1-TDI-Pad8)") (class "Default")
      (node (ref "X1") (pin "8") (pinfunction "TDI_8") (pintype "bidirectional"))
    )
    (net (code "87") (name "unconnected-(X3-PadID)") (class "Default")
      (node (ref "X3") (pin "ID") (pinfunction "ID_ID") (pintype "bidirectional"))
    )
  )
)
